# Warmie_Helper_Board_V_9_4_GND_EN_3_3v.net
KiCad netlist of a schematic drawn in EAGLE
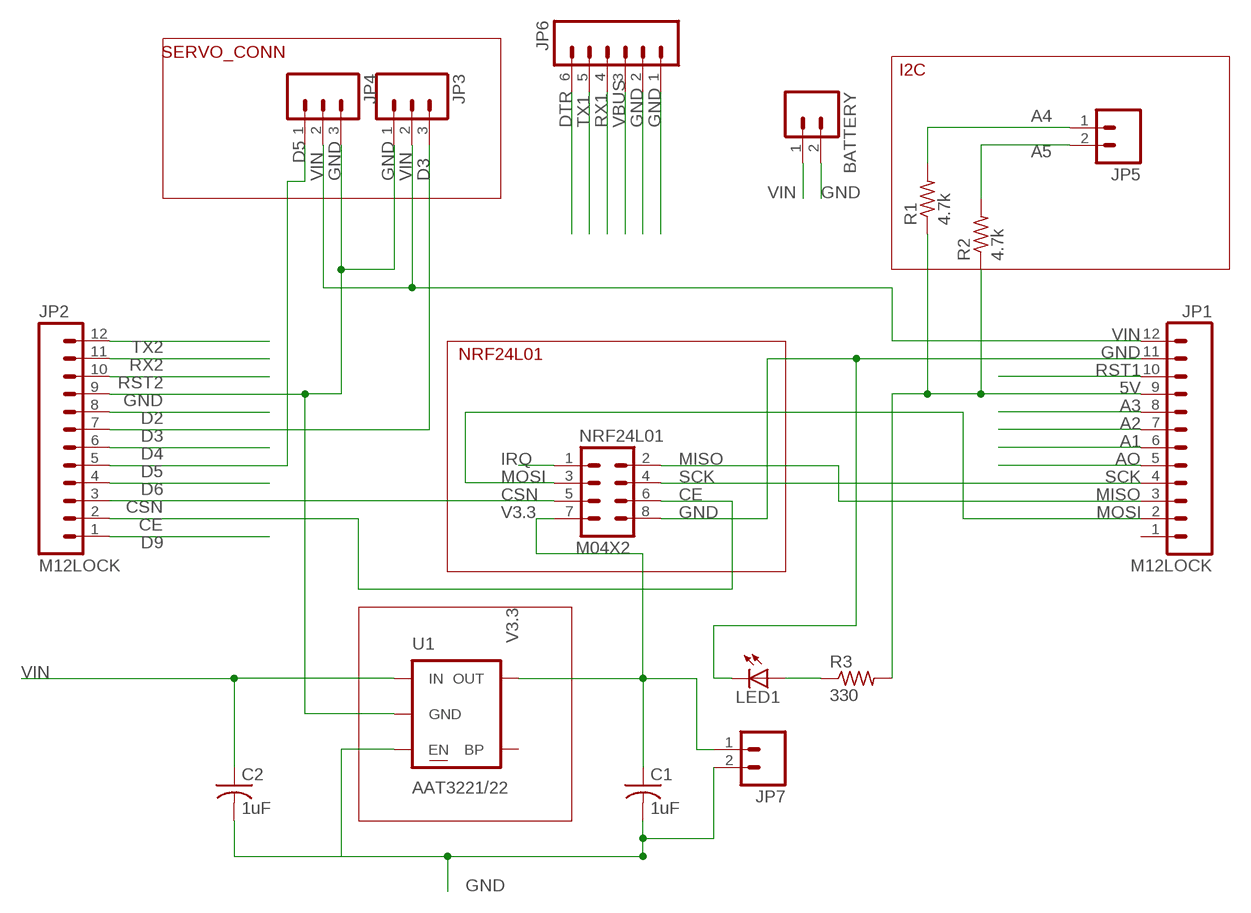
[diagram p0: schematic, sheet 1]

(export (version "E")
  (design (tool "Eeschema 10.0.6"))
  (components
    (comp (ref "BATTERY")
      (value "M02LOCK")
      (footprint "eagle-import:1X02_LOCK")
      (libsource (lib "eagle-import") (part "M02LOCK"))
    )
    (comp (ref "C1")
      (value "1uF")
      (footprint "eagle-import:C0805")
      (libsource (lib "eagle-import") (part "C-USC0805"))
    )
    (comp (ref "C2")
      (value "1uF")
      (footprint "eagle-import:C0805")
      (libsource (lib "eagle-import") (part "C-USC0805"))
    )
    (comp (ref "JP1")
      (value "M12LOCK")
      (footprint "eagle-import:1X12_LOCK")
      (libsource (lib "eagle-import") (part "M12LOCK"))
    )
    (comp (ref "JP2")
      (value "M12LOCK")
      (footprint "eagle-import:1X12_LOCK")
      (libsource (lib "eagle-import") (part "M12LOCK"))
    )
    (comp (ref "JP3")
      (value "M03LOCK")
      (footprint "eagle-import:1X03_LOCK")
      (libsource (lib "eagle-import") (part "M03LOCK"))
    )
    (comp (ref "JP4")
      (value "M03LOCK")
      (footprint "eagle-import:1X03_LOCK")
      (libsource (lib "eagle-import") (part "M03LOCK"))
    )
    (comp (ref "JP5")
      (value "M02LOCK")
      (footprint "eagle-import:1X02_LOCK")
      (libsource (lib "eagle-import") (part "M02LOCK"))
    )
    (comp (ref "JP6")
      (value "M06LOCK")
      (footprint "eagle-import:1X06_LOCK")
      (libsource (lib "eagle-import") (part "M06LOCK"))
    )
    (comp (ref "JP7")
      (value "M02LOCK")
      (footprint "eagle-import:1X02_LOCK")
      (libsource (lib "eagle-import") (part "M02LOCK"))
    )
    (comp (ref "LED1")
      (value "LEDSML0603")
      (footprint "eagle-import:SML0603")
      (libsource (lib "eagle-import") (part "LEDSML0603"))
    )
    (comp (ref "NRF24L01")
      (value "M04X2")
      (footprint "eagle-import:2X4")
      (libsource (lib "eagle-import") (part "M04X2"))
    )
    (comp (ref "R1")
      (value "4.7k")
      (footprint "eagle-import:M0805")
      (libsource (lib "eagle-import") (part "R-US_M0805"))
    )
    (comp (ref "R2")
      (value "4.7k")
      (footprint "eagle-import:M0805")
      (libsource (lib "eagle-import") (part "R-US_M0805"))
    )
    (comp (ref "R3")
      (value "330")
      (footprint "eagle-import:M0805")
      (libsource (lib "eagle-import") (part "R-US_M0805"))
    )
    (comp (ref "U1")
      (value "AAT3221/22")
      (footprint "eagle-import:SOT23-5")
      (libsource (lib "eagle-import") (part "V_REG_LDOSMD"))
    )
  )
  (nets
    (net (code "1") (name "/5V") (class "Default")
      (node (ref "JP1") (pin "9") (pinfunction "9_9") (pintype "passive"))
      (node (ref "R1") (pin "1") (pinfunction "1_1") (pintype "passive"))
      (node (ref "R2") (pin "1") (pinfunction "1_1") (pintype "passive"))
      (node (ref "R3") (pin "2") (pinfunction "2_2") (pintype "passive"))
    )
    (net (code "2") (name "/A1") (class "Default")
      (node (ref "JP1") (pin "6") (pinfunction "6_6") (pintype "passive"))
    )
    (net (code "3") (name "/A2") (class "Default")
      (node (ref "JP1") (pin "7") (pinfunction "7_7") (pintype "passive"))
    )
    (net (code "4") (name "/A3") (class "Default")
      (node (ref "JP1") (pin "8") (pinfunction "8_8") (pintype "passive"))
    )
    (net (code "5") (name "/A4") (class "Default")
      (node (ref "JP5") (pin "1") (pinfunction "1_1") (pintype "passive"))
      (node (ref "R1") (pin "2") (pinfunction "2_2") (pintype "passive"))
    )
    (net (code "6") (name "/A5") (class "Default")
      (node (ref "JP5") (pin "2") (pinfunction "2_2") (pintype "passive"))
      (node (ref "R2") (pin "2") (pinfunction "2_2") (pintype "passive"))
    )
    (net (code "7") (name "/AO") (class "Default")
      (node (ref "JP1") (pin "5") (pinfunction "5_5") (pintype "passive"))
    )
    (net (code "8") (name "/CE") (class "Default")
      (node (ref "JP2") (pin "2") (pinfunction "2_2") (pintype "passive"))
      (node (ref "NRF24L01") (pin "6") (pinfunction "6_6") (pintype "passive"))
    )
    (net (code "9") (name "/CSN") (class "Default")
      (node (ref "JP2") (pin "3") (pinfunction "3_3") (pintype "passive"))
      (node (ref "NRF24L01") (pin "5") (pinfunction "5_5") (pintype "passive"))
    )
    (net (code "10") (name "/D2") (class "Default")
      (node (ref "JP2") (pin "8") (pinfunction "8_8") (pintype "passive"))
    )
    (net (code "11") (name "/D3") (class "Default")
      (node (ref "JP2") (pin "7") (pinfunction "7_7") (pintype "passive"))
      (node (ref "JP3") (pin "3") (pinfunction "3_3") (pintype "passive"))
    )
    (net (code "12") (name "/D4") (class "Default")
      (node (ref "JP2") (pin "6") (pinfunction "6_6") (pintype "passive"))
    )
    (net (code "13") (name "/D5") (class "Default")
      (node (ref "JP2") (pin "5") (pinfunction "5_5") (pintype "passive"))
      (node (ref "JP4") (pin "1") (pinfunction "1_1") (pintype "passive"))
    )
    (net (code "14") (name "/D6") (class "Default")
      (node (ref "JP2") (pin "4") (pinfunction "4_4") (pintype "passive"))
    )
    (net (code "15") (name "/D9") (class "Default")
      (node (ref "JP2") (pin "1") (pinfunction "1_1") (pintype "passive"))
    )
    (net (code "16") (name "/DTR") (class "Default")
      (node (ref "JP6") (pin "6") (pinfunction "6_6") (pintype "passive"))
    )
    (net (code "17") (name "/GND") (class "Default")
      (node (ref "BATTERY") (pin "2") (pinfunction "2_2") (pintype "passive"))
      (node (ref "C1") (pin "2") (pinfunction "2_2") (pintype "passive"))
      (node (ref "C2") (pin "2") (pinfunction "2_2") (pintype "passive"))
      (node (ref "JP1") (pin "11") (pinfunction "11_11") (pintype "passive"))
      (node (ref "JP2") (pin "9") (pinfunction "9_9") (pintype "passive"))
      (node (ref "JP3") (pin "1") (pinfunction "1_1") (pintype "passive"))
      (node (ref "JP4") (pin "3") (pinfunction "3_3") (pintype "passive"))
      (node (ref "JP6") (pin "1") (pinfunction "1_1") (pintype "passive"))
      (node (ref "JP6") (pin "2") (pinfunction "2_2") (pintype "passive"))
      (node (ref "JP7") (pin "2") (pinfunction "2_2") (pintype "passive"))
      (node (ref "LED1") (pin "C") (pinfunction "C_C") (pintype "passive"))
      (node (ref "NRF24L01") (pin "8") (pinfunction "8_8") (pintype "passive"))
      (node (ref "U1") (pin "2") (pinfunction "GND_2") (pintype "input"))
      (node (ref "U1") (pin "3") (pinfunction "EN_3") (pintype "input"))
    )
    (net (code "18") (name "/IRQ") (class "Default")
      (node (ref "NRF24L01") (pin "1") (pinfunction "1_1") (pintype "passive"))
    )
    (net (code "19") (name "/MISO") (class "Default")
      (node (ref "JP1") (pin "3") (pinfunction "3_3") (pintype "passive"))
      (node (ref "NRF24L01") (pin "2") (pinfunction "2_2") (pintype "passive"))
    )
    (net (code "20") (name "/MOSI") (class "Default")
      (node (ref "JP1") (pin "2") (pinfunction "2_2") (pintype "passive"))
      (node (ref "NRF24L01") (pin "3") (pinfunction "3_3") (pintype "passive"))
    )
    (net (code "21") (name "/RST1") (class "Default")
      (node (ref "JP1") (pin "10") (pinfunction "10_10") (pintype "passive"))
    )
    (net (code "22") (name "/RST2") (class "Default")
      (node (ref "JP2") (pin "10") (pinfunction "10_10") (pintype "passive"))
    )
    (net (code "23") (name "/RX1") (class "Default")
      (node (ref "JP6") (pin "4") (pinfunction "4_4") (pintype "passive"))
    )
    (net (code "24") (name "/RX2") (class "Default")
      (node (ref "JP2") (pin "11") (pinfunction "11_11") (pintype "passive"))
    )
    (net (code "25") (name "/SCK") (class "Default")
      (node (ref "JP1") (pin "4") (pinfunction "4_4") (pintype "passive"))
      (node (ref "NRF24L01") (pin "4") (pinfunction "4_4") (pintype "passive"))
    )
    (net (code "26") (name "/TX1") (class "Default")
      (node (ref "JP6") (pin "5") (pinfunction "5_5") (pintype "passive"))
    )
    (net (code "27") (name "/TX2") (class "Default")
      (node (ref "JP2") (pin "12") (pinfunction "12_12") (pintype "passive"))
    )
    (net (code "28") (name "/V3.3") (class "Default")
      (node (ref "C1") (pin "1") (pinfunction "1_1") (pintype "passive"))
      (node (ref "JP7") (pin "1") (pinfunction "1_1") (pintype "passive"))
      (node (ref "NRF24L01") (pin "7") (pinfunction "7_7") (pintype "passive"))
      (node (ref "U1") (pin "5") (pinfunction "OUT_5") (pintype "passive"))
    )
    (net (code "29") (name "/VBUS") (class "Default")
      (node (ref "JP6") (pin "3") (pinfunction "3_3") (pintype "passive"))
    )
    (net (code "30") (name "/VIN") (class "Default")
      (node (ref "BATTERY") (pin "1") (pinfunction "1_1") (pintype "passive"))
      (node (ref "C2") (pin "1") (pinfunction "1_1") (pintype "passive"))
      (node (ref "JP1") (pin "12") (pinfunction "12_12") (pintype "passive"))
      (node (ref "JP3") (pin "2") (pinfunction "2_2") (pintype "passive"))
      (node (ref "JP4") (pin "2") (pinfunction "2_2") (pintype "passive"))
      (node (ref "U1") (pin "1") (pinfunction "IN_1") (pintype "input"))
    )
    (net (code "31") (name "Net-(LED1-PadA)") (class "Default")
      (node (ref "LED1") (pin "A") (pinfunction "A_A") (pintype "passive"))
      (node (ref "R3") (pin "1") (pinfunction "1_1") (pintype "passive"))
    )
    (net (code "32") (name "unconnected-(JP1-Pad1)") (class "Default")
      (node (ref "JP1") (pin "1") (pinfunction "1_1") (pintype "passive"))
    )
    (net (code "33") (name "unconnected-(U1-BP-Pad4)") (class "Default")
      (node (ref "U1") (pin "4") (pinfunction "BP_4") (pintype "input"))
    )
  )
)
